# coils.net
KiCad netlist of a schematic drawn in Altium Designer
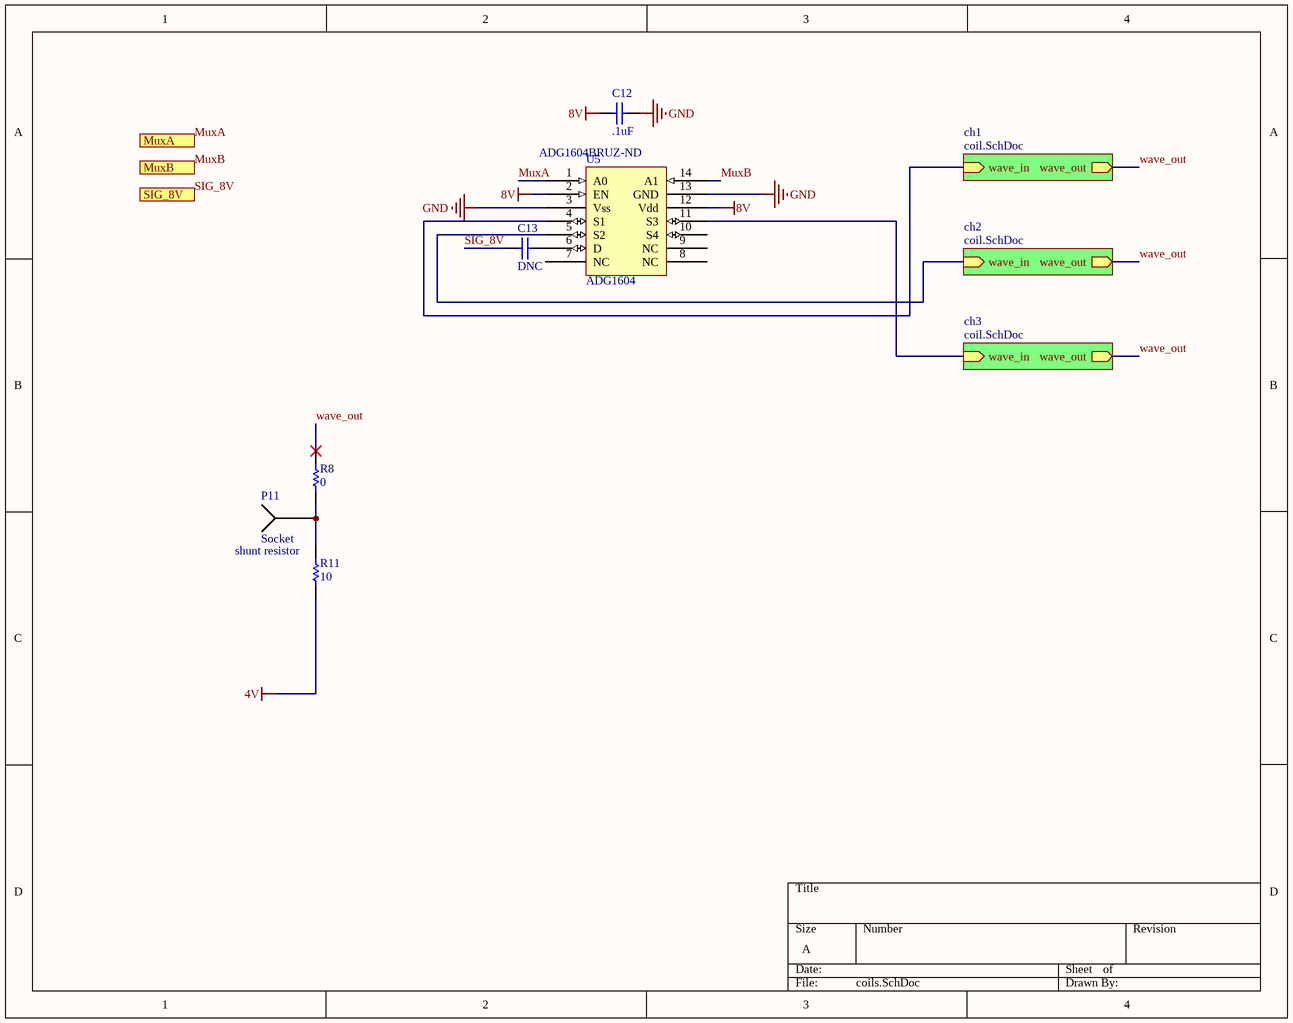
[diagram p0: coils.SchDoc]

(export (version "E")
  (design (tool "Eeschema 10.0.6"))
  (components
    (comp (ref "C12")
      (value ".1uF")
      (footprint "0603")
      (description "Ceramic Capacitor (Surface Mount)")
      (fields (field (name "MANUFACTURER") "Generic Ceramic Chip Cap (TBD)") (field (name "Comment") "Cap"))
      (libsource (lib "maglib") (part "Cap"))
    )
    (comp (ref "C13")
      (value "DNC")
      (footprint "0603")
      (description "Ceramic Capacitor (Surface Mount)")
      (fields (field (name "MANUFACTURER") "Generic Ceramic Chip Cap (TBD)") (field (name "Comment") "Cap"))
      (libsource (lib "maglib") (part "Cap"))
    )
    (comp (ref "P11") (value "Socket") (footprint "socket") (libsource (lib "maglib") (part "Socket")))
    (comp (ref "R8")
      (value "0")
      (footprint "0603")
      (description "Chip Resistor (Surface Mount)")
      (fields (field (name "MANUFACTURER") "Generic Chip Res (TBD)") (field (name "Comment") "Res"))
      (libsource (lib "maglib") (part "Res"))
    )
    (comp (ref "R11")
      (value "10")
      (footprint "0603")
      (description "Chip Resistor (Surface Mount)")
      (fields (field (name "MANUFACTURER") "Generic Chip Res (TBD)") (field (name "Comment") "Res"))
      (libsource (lib "maglib") (part "Res"))
    )
    (comp (ref "U5")
      (value "ADG1604")
      (footprint "TSSOP-14")
      (fields (field (name "SUPPLIER PART NUMBER 1") "ADG1604BRUZ-ND"))
      (libsource (lib "maglib") (part "ADG1604"))
    )
  )
  (nets
    (net (code "1") (name "/MuxA") (class "Default")
      (node (ref "U5") (pin "1") (pinfunction "A0_1") (pintype "input"))
    )
    (net (code "2") (name "/MuxB") (class "Default")
      (node (ref "U5") (pin "14") (pinfunction "A1_14") (pintype "input"))
    )
    (net (code "3") (name "/SIG_8V") (class "Default")
      (node (ref "C13") (pin "1") (pinfunction "1_1") (pintype "passive"))
    )
    (net (code "4") (name "/wave_in") (class "Default")
      (node (ref "U5") (pin "11") (pinfunction "S3_11") (pintype "bidirectional"))
    )
    (net (code "5") (name "/wave_in_1") (class "Default")
      (node (ref "U5") (pin "4") (pinfunction "S1_4") (pintype "bidirectional"))
    )
    (net (code "6") (name "/wave_in_2") (class "Default")
      (node (ref "U5") (pin "5") (pinfunction "S2_5") (pintype "bidirectional"))
    )
    (net (code "7") (name "/wave_out") (class "Default")
      (node (ref "R8") (pin "2") (pinfunction "2_2") (pintype "passive+no_connect"))
    )
    (net (code "8") (name "4V") (class "Default")
      (node (ref "R11") (pin "1") (pinfunction "1_1") (pintype "passive"))
    )
    (net (code "9") (name "8V") (class "Default")
      (node (ref "C12") (pin "1") (pinfunction "1_1") (pintype "passive"))
      (node (ref "U5") (pin "12") (pinfunction "Vdd_12") (pintype "power_in"))
      (node (ref "U5") (pin "2") (pinfunction "EN_2") (pintype "input"))
    )
    (net (code "10") (name "GND") (class "Default")
      (node (ref "C12") (pin "2") (pinfunction "2_2") (pintype "passive"))
      (node (ref "U5") (pin "13") (pinfunction "GND_13") (pintype "power_in"))
      (node (ref "U5") (pin "3") (pinfunction "Vss_3") (pintype "power_in"))
    )
    (net (code "11") (name "Net-(P11-Pad0)") (class "Default")
      (node (ref "P11") (pin "0") (pinfunction "0_0") (pintype "passive"))
      (node (ref "R11") (pin "2") (pinfunction "2_2") (pintype "passive"))
      (node (ref "R8") (pin "1") (pinfunction "1_1") (pintype "passive"))
    )
    (net (code "12") (name "Net-(U5-D)") (class "Default")
      (node (ref "C13") (pin "2") (pinfunction "2_2") (pintype "passive"))
      (node (ref "U5") (pin "6") (pinfunction "D_6") (pintype "bidirectional"))
    )
    (net (code "13") (name "unconnected-(U5-NC-Pad7)") (class "Default")
      (node (ref "U5") (pin "7") (pinfunction "NC_7") (pintype "passive"))
    )
    (net (code "14") (name "unconnected-(U5-NC-Pad8)") (class "Default")
      (node (ref "U5") (pin "8") (pinfunction "NC_8") (pintype "passive"))
    )
    (net (code "15") (name "unconnected-(U5-NC-Pad9)") (class "Default")
      (node (ref "U5") (pin "9") (pinfunction "NC_9") (pintype "passive"))
    )
    (net (code "16") (name "unconnected-(U5-S4-Pad10)") (class "Default")
      (node (ref "U5") (pin "10") (pinfunction "S4_10") (pintype "bidirectional"))
    )
  )
)
